# voltage_regulator.net
KiCad netlist of a schematic drawn in EAGLE
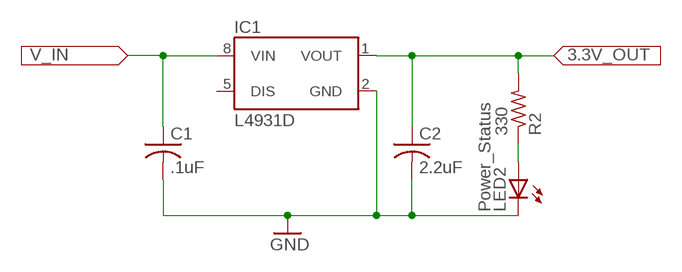
[diagram p0: schematic, sheet 1]

(export (version "E")
  (design (tool "Eeschema 10.0.6"))
  (components
    (comp (ref "C1")
      (value ".1uF")
      (footprint "eagle-import:C050-024X044")
      (libsource (lib "eagle-import") (part "C-US050-024X044"))
    )
    (comp (ref "C2")
      (value "2.2uF")
      (footprint "eagle-import:C050-024X044")
      (libsource (lib "eagle-import") (part "C-US050-024X044"))
    )
    (comp (ref "IC1")
      (value "L4931D")
      (footprint "eagle-import:SO08")
      (libsource (lib "eagle-import") (part "L4931D"))
    )
    (comp (ref "LED2")
      (value "Power_Status")
      (footprint "eagle-import:NFSG036BT")
      (libsource (lib "eagle-import") (part "NFSG036BT"))
    )
    (comp (ref "R2")
      (value "330")
      (footprint "eagle-import:R0805")
      (libsource (lib "eagle-import") (part "R-US_R0805"))
    )
  )
  (nets
    (net (code "1") (name "GND") (class "Default")
      (node (ref "C1") (pin "2") (pinfunction "2_2") (pintype "passive"))
      (node (ref "C2") (pin "2") (pinfunction "2_2") (pintype "passive"))
      (node (ref "IC1") (pin "2") (pinfunction "GND_2") (pintype "power_in"))
      (node (ref "LED2") (pin "C") (pinfunction "C_C") (pintype "passive"))
    )
    (net (code "2") (name "Net-(IC1-VIN)") (class "Default")
      (node (ref "C1") (pin "1") (pinfunction "1_1") (pintype "passive"))
      (node (ref "IC1") (pin "8") (pinfunction "VIN_8") (pintype "power_in"))
    )
    (net (code "3") (name "Net-(IC1-VOUT)") (class "Default")
      (node (ref "C2") (pin "1") (pinfunction "1_1") (pintype "passive"))
      (node (ref "IC1") (pin "1") (pinfunction "VOUT_1") (pintype "power_in"))
      (node (ref "R2") (pin "2") (pinfunction "2_2") (pintype "passive"))
    )
    (net (code "4") (name "Net-(LED2-PadA)") (class "Default")
      (node (ref "LED2") (pin "A") (pinfunction "A_A") (pintype "passive"))
      (node (ref "R2") (pin "1") (pinfunction "1_1") (pintype "passive"))
    )
    (net (code "5") (name "unconnected-(IC1-DIS-Pad5)") (class "Default")
      (node (ref "IC1") (pin "5") (pinfunction "DIS_5") (pintype "passive"))
    )
  )
)
